# Main_v0_1.net
KiCad netlist of a schematic drawn in Altium Designer
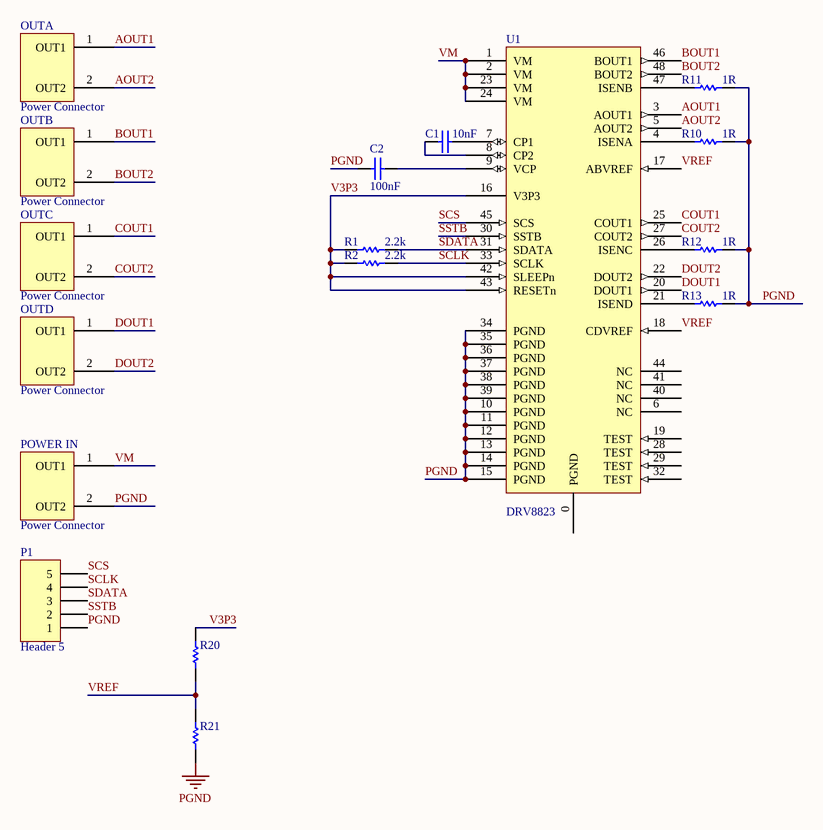
[diagram p0: Main_v0.1.SchDoc]

(export (version "E")
  (design (tool "Eeschema 10.0.6"))
  (components
    (comp (ref "C1")
      (value "10nF")
      (footprint "C1206")
      (description "Capacitor (Semiconductor SIM Model)")
      (fields (field (name "Comment") "Cap Semi") (field (name "PUBLISHER") "Altium Limited"))
      (libsource (lib "Miscellaneous Devices") (part "Cap Semi"))
    )
    (comp (ref "C2")
      (value "100nF")
      (footprint "C1206")
      (description "Capacitor (Semiconductor SIM Model)")
      (fields (field (name "Comment") "Cap Semi") (field (name "PUBLISHER") "Altium Limited"))
      (libsource (lib "Miscellaneous Devices") (part "Cap Semi"))
    )
    (comp (ref "OUTA")
      (value "Power Connector")
      (footprint "PCBComponent_1")
      (libsource (lib "IntegratedCircuit") (part "Power Connector"))
    )
    (comp (ref "OUTB")
      (value "Power Connector")
      (footprint "PCBComponent_1")
      (libsource (lib "IntegratedCircuit") (part "Power Connector"))
    )
    (comp (ref "OUTC")
      (value "Power Connector")
      (footprint "PCBComponent_1")
      (libsource (lib "IntegratedCircuit") (part "Power Connector"))
    )
    (comp (ref "OUTD")
      (value "Power Connector")
      (footprint "PCBComponent_1")
      (libsource (lib "IntegratedCircuit") (part "Power Connector"))
    )
    (comp (ref "P1")
      (value "Header 5")
      (footprint "HDR1X5")
      (description "Header, 5-Pin")
      (fields (field (name "PUBLISHER") "Altium Limited"))
      (libsource (lib "Miscellaneous Connectors") (part "Header 5"))
    )
    (comp (ref "POWER IN")
      (value "Power Connector")
      (footprint "PCBComponent_1")
      (libsource (lib "IntegratedCircuit") (part "Power Connector"))
    )
    (comp (ref "R1")
      (value "2.2k")
      (footprint "AXIAL-0.3")
      (description "Resistor")
      (fields (field (name "Comment") "Res1") (field (name "PUBLISHER") "Altium Limited"))
      (libsource (lib "Miscellaneous Devices") (part "Res1"))
    )
    (comp (ref "R2")
      (value "2.2k")
      (footprint "AXIAL-0.3")
      (description "Resistor")
      (fields (field (name "Comment") "Res1") (field (name "PUBLISHER") "Altium Limited"))
      (libsource (lib "Miscellaneous Devices") (part "Res1"))
    )
    (comp (ref "R10")
      (value "1R")
      (footprint "AXIAL-0.3")
      (description "Resistor")
      (fields (field (name "Comment") "Res1") (field (name "PUBLISHER") "Altium Limited"))
      (libsource (lib "Miscellaneous Devices") (part "Res1"))
    )
    (comp (ref "R11")
      (value "1R")
      (footprint "AXIAL-0.3")
      (description "Resistor")
      (fields (field (name "Comment") "Res1") (field (name "PUBLISHER") "Altium Limited"))
      (libsource (lib "Miscellaneous Devices") (part "Res1"))
    )
    (comp (ref "R12")
      (value "1R")
      (footprint "AXIAL-0.3")
      (description "Resistor")
      (fields (field (name "Comment") "Res1") (field (name "PUBLISHER") "Altium Limited"))
      (libsource (lib "Miscellaneous Devices") (part "Res1"))
    )
    (comp (ref "R13")
      (value "1R")
      (footprint "AXIAL-0.3")
      (description "Resistor")
      (fields (field (name "Comment") "Res1") (field (name "PUBLISHER") "Altium Limited"))
      (libsource (lib "Miscellaneous Devices") (part "Res1"))
    )
    (comp (ref "R20")
      (value "Res1")
      (footprint "AXIAL-0.3")
      (description "Resistor")
      (fields (field (name "PUBLISHER") "Altium Limited"))
      (libsource (lib "Miscellaneous Devices") (part "Res1"))
    )
    (comp (ref "R21")
      (value "Res1")
      (footprint "AXIAL-0.3")
      (description "Resistor")
      (fields (field (name "PUBLISHER") "Altium Limited"))
      (libsource (lib "Miscellaneous Devices") (part "Res1"))
    )
    (comp (ref "U1")
      (value "DRV8823")
      (footprint "TSSOP50P810X120_HS-49N")
      (description "4-BRIDGE  SERIAL  INTERFACE  MOTOR  DRIVER")
      (libsource (lib "IntegratedCircuit") (part "DRV8823"))
    )
  )
  (nets
    (net (code "1") (name "/AOUT1") (class "Default")
      (node (ref "OUTA") (pin "1") (pinfunction "OUT1_1") (pintype "power_in"))
      (node (ref "U1") (pin "3") (pinfunction "AOUT1_3") (pintype "output"))
    )
    (net (code "2") (name "/AOUT2") (class "Default")
      (node (ref "OUTA") (pin "2") (pinfunction "OUT2_2") (pintype "power_in"))
      (node (ref "U1") (pin "5") (pinfunction "AOUT2_5") (pintype "output"))
    )
    (net (code "3") (name "/BOUT1") (class "Default")
      (node (ref "OUTB") (pin "1") (pinfunction "OUT1_1") (pintype "power_in"))
      (node (ref "U1") (pin "46") (pinfunction "BOUT1_46") (pintype "output"))
    )
    (net (code "4") (name "/BOUT2") (class "Default")
      (node (ref "OUTB") (pin "2") (pinfunction "OUT2_2") (pintype "power_in"))
      (node (ref "U1") (pin "48") (pinfunction "BOUT2_48") (pintype "output"))
    )
    (net (code "5") (name "/COUT1") (class "Default")
      (node (ref "OUTC") (pin "1") (pinfunction "OUT1_1") (pintype "power_in"))
      (node (ref "U1") (pin "25") (pinfunction "COUT1_25") (pintype "output"))
    )
    (net (code "6") (name "/COUT2") (class "Default")
      (node (ref "OUTC") (pin "2") (pinfunction "OUT2_2") (pintype "power_in"))
      (node (ref "U1") (pin "27") (pinfunction "COUT2_27") (pintype "output"))
    )
    (net (code "7") (name "/DOUT1") (class "Default")
      (node (ref "OUTD") (pin "1") (pinfunction "OUT1_1") (pintype "power_in"))
      (node (ref "U1") (pin "20") (pinfunction "DOUT1_20") (pintype "output"))
    )
    (net (code "8") (name "/DOUT2") (class "Default")
      (node (ref "OUTD") (pin "2") (pinfunction "OUT2_2") (pintype "power_in"))
      (node (ref "U1") (pin "22") (pinfunction "DOUT2_22") (pintype "output"))
    )
    (net (code "9") (name "/SCLK") (class "Default")
      (node (ref "P1") (pin "4") (pinfunction "4_4") (pintype "passive"))
      (node (ref "R2") (pin "2") (pinfunction "2_2") (pintype "passive"))
      (node (ref "U1") (pin "33") (pinfunction "SCLK_33") (pintype "input"))
    )
    (net (code "10") (name "/SCS") (class "Default")
      (node (ref "P1") (pin "5") (pinfunction "5_5") (pintype "passive"))
      (node (ref "U1") (pin "45") (pinfunction "SCS_45") (pintype "input"))
    )
    (net (code "11") (name "/SDATA") (class "Default")
      (node (ref "P1") (pin "3") (pinfunction "3_3") (pintype "passive"))
      (node (ref "R1") (pin "2") (pinfunction "2_2") (pintype "passive"))
      (node (ref "U1") (pin "31") (pinfunction "SDATA_31") (pintype "input"))
    )
    (net (code "12") (name "/SSTB") (class "Default")
      (node (ref "P1") (pin "2") (pinfunction "2_2") (pintype "passive"))
      (node (ref "U1") (pin "30") (pinfunction "SSTB_30") (pintype "input"))
    )
    (net (code "13") (name "/V3P3") (class "Default")
      (node (ref "R1") (pin "1") (pinfunction "1_1") (pintype "passive"))
      (node (ref "R2") (pin "1") (pinfunction "1_1") (pintype "passive"))
      (node (ref "R20") (pin "2") (pinfunction "2_2") (pintype "passive"))
      (node (ref "U1") (pin "16") (pinfunction "V3P3_16") (pintype "power_in"))
      (node (ref "U1") (pin "42") (pinfunction "SLEEPn_42") (pintype "input"))
      (node (ref "U1") (pin "43") (pinfunction "RESETn_43") (pintype "input"))
    )
    (net (code "14") (name "/VM") (class "Default")
      (node (ref "POWER IN") (pin "1") (pinfunction "OUT1_1") (pintype "power_in"))
      (node (ref "U1") (pin "1") (pinfunction "VM_1") (pintype "power_in"))
      (node (ref "U1") (pin "2") (pinfunction "VM_2") (pintype "power_in"))
      (node (ref "U1") (pin "23") (pinfunction "VM_23") (pintype "power_in"))
      (node (ref "U1") (pin "24") (pinfunction "VM_24") (pintype "power_in"))
    )
    (net (code "15") (name "/VREF") (class "Default")
      (node (ref "R20") (pin "1") (pinfunction "1_1") (pintype "passive"))
      (node (ref "R21") (pin "2") (pinfunction "2_2") (pintype "passive"))
      (node (ref "U1") (pin "17") (pinfunction "ABVREF_17") (pintype "input"))
      (node (ref "U1") (pin "18") (pinfunction "CDVREF_18") (pintype "input"))
    )
    (net (code "16") (name "Net-(U1-CP1)") (class "Default")
      (node (ref "C1") (pin "2") (pinfunction "2_2") (pintype "passive"))
      (node (ref "U1") (pin "7") (pinfunction "CP1_7") (pintype "bidirectional"))
    )
    (net (code "17") (name "Net-(U1-CP2)") (class "Default")
      (node (ref "C1") (pin "1") (pinfunction "1_1") (pintype "passive"))
      (node (ref "U1") (pin "8") (pinfunction "CP2_8") (pintype "bidirectional"))
    )
    (net (code "18") (name "Net-(U1-ISENA)") (class "Default")
      (node (ref "R10") (pin "1") (pinfunction "1_1") (pintype "passive"))
      (node (ref "U1") (pin "4") (pinfunction "ISENA_4") (pintype "passive"))
    )
    (net (code "19") (name "Net-(U1-ISENB)") (class "Default")
      (node (ref "R11") (pin "1") (pinfunction "1_1") (pintype "passive"))
      (node (ref "U1") (pin "47") (pinfunction "ISENB_47") (pintype "passive"))
    )
    (net (code "20") (name "Net-(U1-ISENC)") (class "Default")
      (node (ref "R12") (pin "1") (pinfunction "1_1") (pintype "passive"))
      (node (ref "U1") (pin "26") (pinfunction "ISENC_26") (pintype "passive"))
    )
    (net (code "21") (name "Net-(U1-ISEND)") (class "Default")
      (node (ref "R13") (pin "1") (pinfunction "1_1") (pintype "passive"))
      (node (ref "U1") (pin "21") (pinfunction "ISEND_21") (pintype "passive"))
    )
    (net (code "22") (name "Net-(U1-VCP)") (class "Default")
      (node (ref "C2") (pin "2") (pinfunction "2_2") (pintype "passive"))
      (node (ref "U1") (pin "9") (pinfunction "VCP_9") (pintype "bidirectional"))
    )
    (net (code "23") (name "PGND") (class "Default")
      (node (ref "C2") (pin "1") (pinfunction "1_1") (pintype "passive"))
      (node (ref "P1") (pin "1") (pinfunction "1_1") (pintype "passive"))
      (node (ref "POWER IN") (pin "2") (pinfunction "OUT2_2") (pintype "power_in"))
      (node (ref "R10") (pin "2") (pinfunction "2_2") (pintype "passive"))
      (node (ref "R11") (pin "2") (pinfunction "2_2") (pintype "passive"))
      (node (ref "R12") (pin "2") (pinfunction "2_2") (pintype "passive"))
      (node (ref "R13") (pin "2") (pinfunction "2_2") (pintype "passive"))
      (node (ref "R21") (pin "1") (pinfunction "1_1") (pintype "passive"))
      (node (ref "U1") (pin "10") (pinfunction "PGND_10") (pintype "power_in"))
      (node (ref "U1") (pin "11") (pinfunction "PGND_11") (pintype "power_in"))
      (node (ref "U1") (pin "12") (pinfunction "PGND_12") (pintype "power_in"))
      (node (ref "U1") (pin "13") (pinfunction "PGND_13") (pintype "power_in"))
      (node (ref "U1") (pin "14") (pinfunction "PGND_14") (pintype "power_in"))
      (node (ref "U1") (pin "15") (pinfunction "PGND_15") (pintype "power_in"))
      (node (ref "U1") (pin "34") (pinfunction "PGND_34") (pintype "power_in"))
      (node (ref "U1") (pin "35") (pinfunction "PGND_35") (pintype "power_in"))
      (node (ref "U1") (pin "36") (pinfunction "PGND_36") (pintype "power_in"))
      (node (ref "U1") (pin "37") (pinfunction "PGND_37") (pintype "power_in"))
      (node (ref "U1") (pin "38") (pinfunction "PGND_38") (pintype "power_in"))
      (node (ref "U1") (pin "39") (pinfunction "PGND_39") (pintype "power_in"))
    )
    (net (code "24") (name "unconnected-(U1-NC-Pad6)") (class "Default")
      (node (ref "U1") (pin "6") (pinfunction "NC_6") (pintype "passive"))
    )
    (net (code "25") (name "unconnected-(U1-NC-Pad40)") (class "Default")
      (node (ref "U1") (pin "40") (pinfunction "NC_40") (pintype "passive"))
    )
    (net (code "26") (name "unconnected-(U1-NC-Pad41)") (class "Default")
      (node (ref "U1") (pin "41") (pinfunction "NC_41") (pintype "passive"))
    )
    (net (code "27") (name "unconnected-(U1-NC-Pad44)") (class "Default")
      (node (ref "U1") (pin "44") (pinfunction "NC_44") (pintype "passive"))
    )
    (net (code "28") (name "unconnected-(U1-PGND-Pad0)") (class "Default")
      (node (ref "U1") (pin "0") (pinfunction "PGND_0") (pintype "power_in"))
    )
    (net (code "29") (name "unconnected-(U1-TEST-Pad19)") (class "Default")
      (node (ref "U1") (pin "19") (pinfunction "TEST_19") (pintype "input"))
    )
    (net (code "30") (name "unconnected-(U1-TEST-Pad28)") (class "Default")
      (node (ref "U1") (pin "28") (pinfunction "TEST_28") (pintype "input"))
    )
    (net (code "31") (name "unconnected-(U1-TEST-Pad29)") (class "Default")
      (node (ref "U1") (pin "29") (pinfunction "TEST_29") (pintype "input"))
    )
    (net (code "32") (name "unconnected-(U1-TEST-Pad32)") (class "Default")
      (node (ref "U1") (pin "32") (pinfunction "TEST_32") (pintype "input"))
    )
  )
)
